# Power.net
KiCad netlist of a schematic drawn in Altium Designer
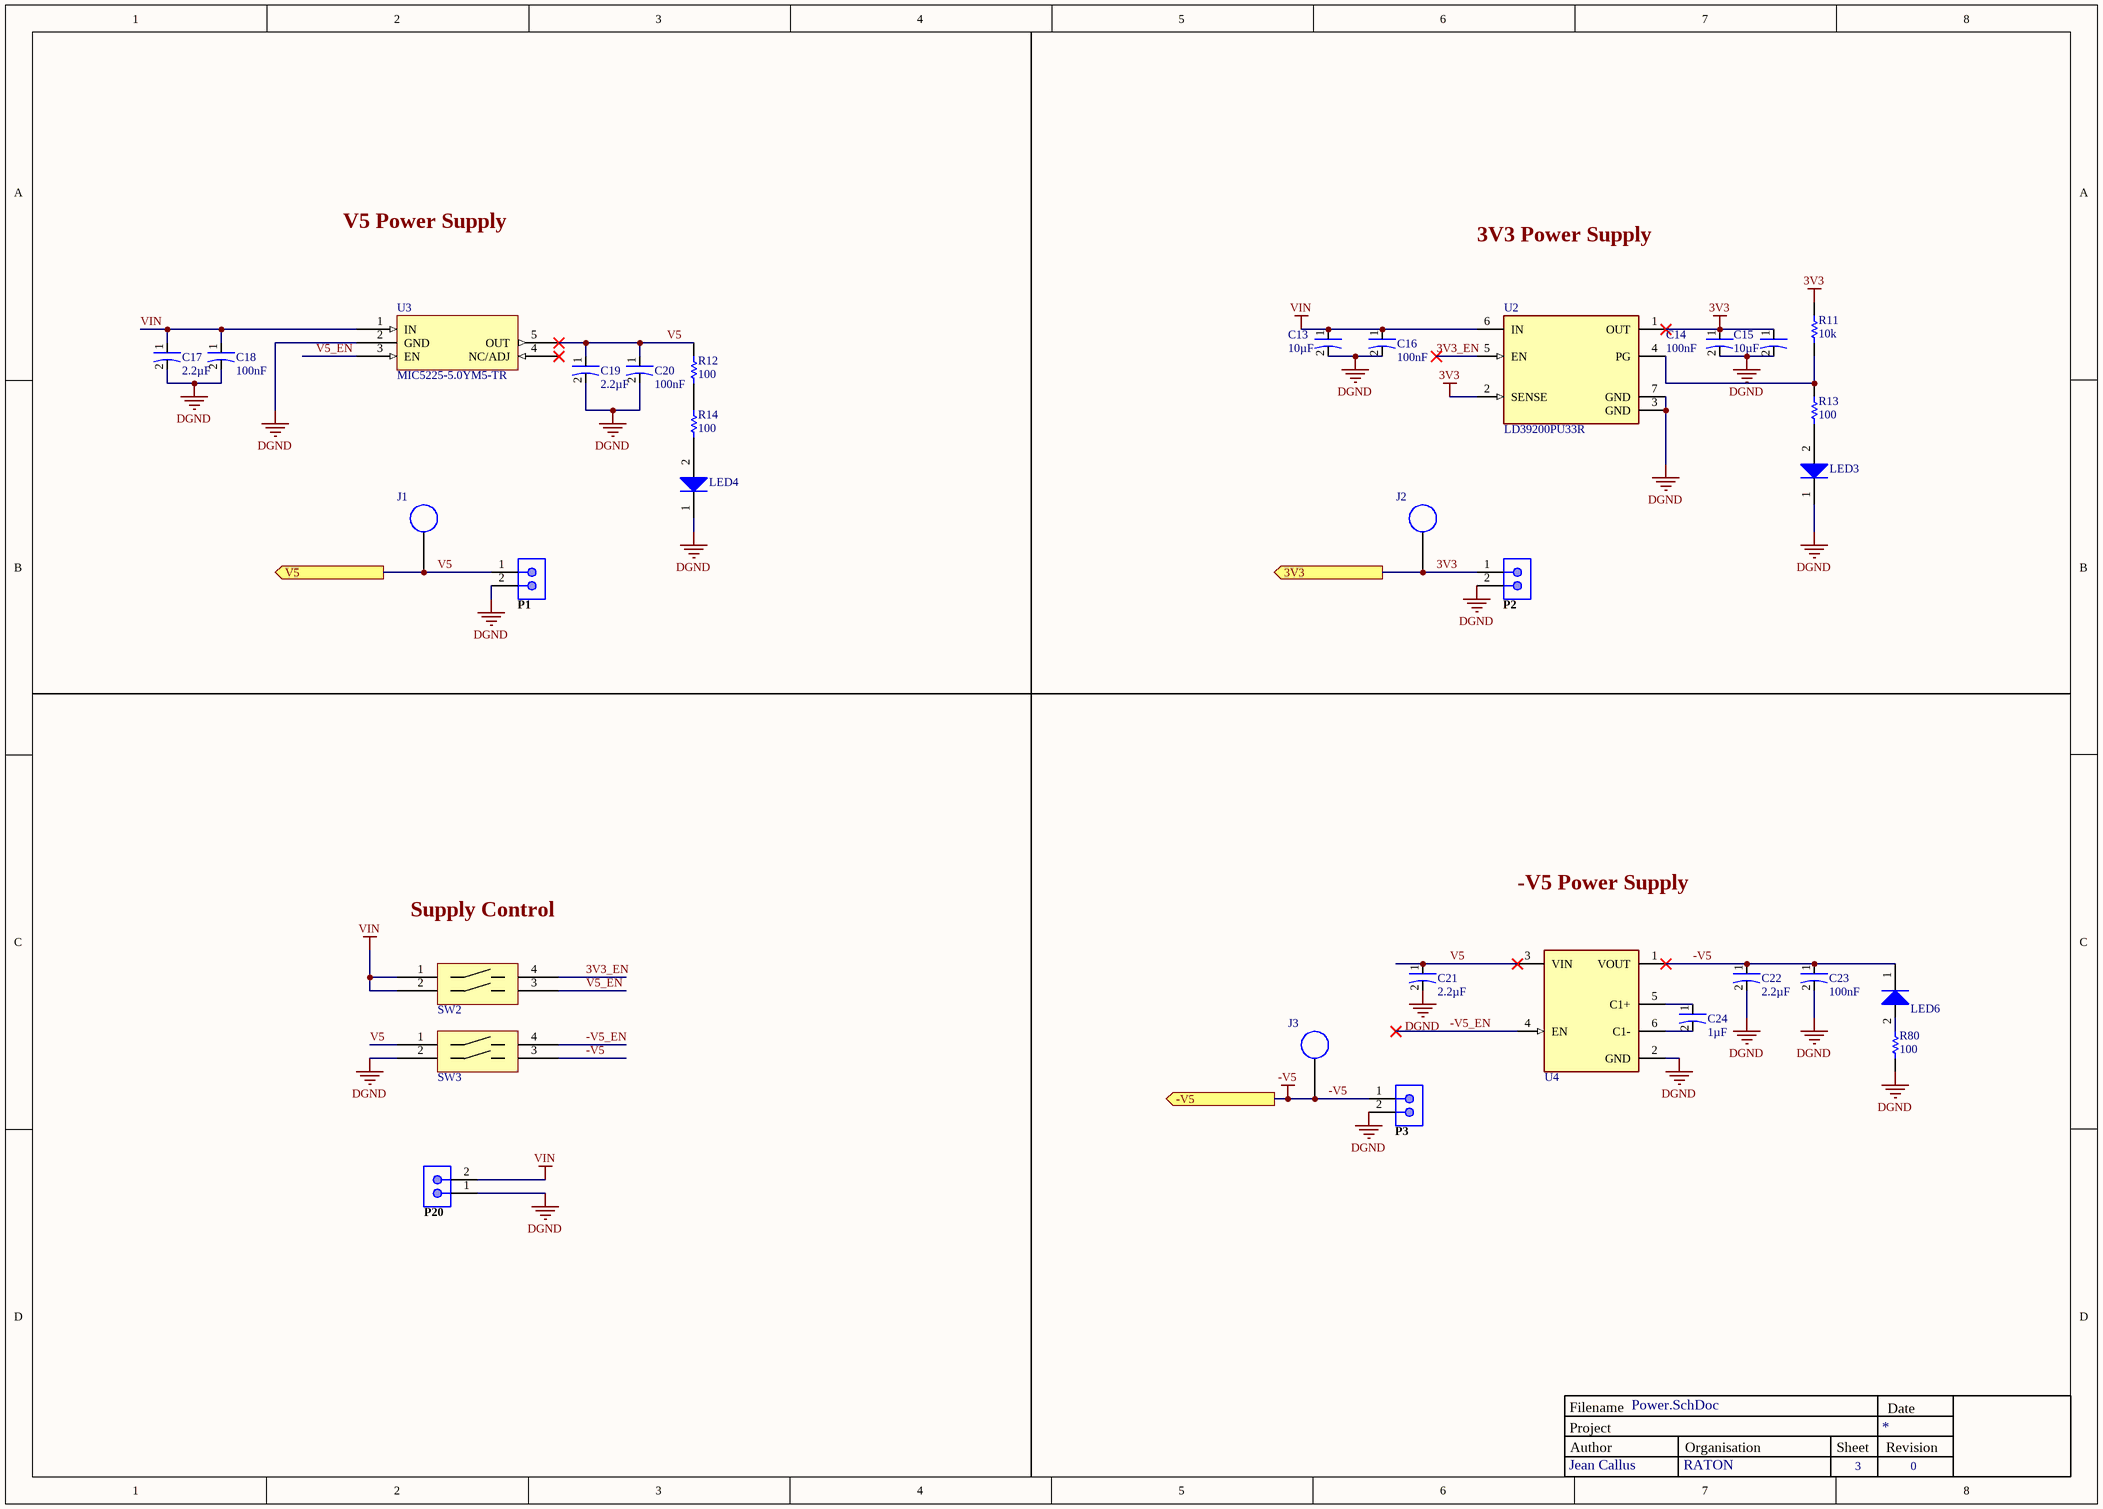
[diagram p0: Power.SchDoc]

(export (version "E")
  (design (tool "Eeschema 10.0.6"))
  (components
    (comp (ref "C13")
      (value "10µF")
      (footprint "0402-M")
      (description "CAP-10uF-CER-0402-6.3V-X5R-20%")
      (fields
        (field (name "MANUFACTURER") "Generic")
        (field (name "Comment") "CAP 10uF CER 0402 6.3V X5R 20%")
      )
      (libsource (lib "") (part "Symbol_1"))
    )
    (comp (ref "C14")
      (value "100nF")
      (footprint "0805-M")
      (description "CAP-0.1uF-CER-0805-50V-X7R-10%")
      (fields
        (field (name "MANUFACTURER") "Generic")
        (field (name "Comment") "CAP 0.1uF CER 0805 50V X7R 10%")
      )
      (libsource (lib "") (part "Symbol_1"))
    )
    (comp (ref "C15")
      (value "10µF")
      (footprint "0402-M")
      (description "CAP-10uF-CER-0402-6.3V-X5R-20%")
      (fields
        (field (name "MANUFACTURER") "Generic")
        (field (name "Comment") "CAP 10uF CER 0402 6.3V X5R 20%")
      )
      (libsource (lib "") (part "Symbol_1"))
    )
    (comp (ref "C16")
      (value "100nF")
      (footprint "0805-M")
      (description "CAP-0.1uF-CER-0805-50V-X7R-10%")
      (fields
        (field (name "MANUFACTURER") "Generic")
        (field (name "Comment") "CAP 0.1uF CER 0805 50V X7R 10%")
      )
      (libsource (lib "") (part "Symbol_1"))
    )
    (comp (ref "C17")
      (value "2.2µF")
      (footprint "0402-M")
      (description "CAP-2.2uF-CER-0402-25V-X5R-10%")
      (fields
        (field (name "MANUFACTURER") "Generic")
        (field (name "Comment") "CAP 2.2uF CER 0402 25V X5R 10%")
      )
      (libsource (lib "") (part "Symbol_1"))
    )
    (comp (ref "C18")
      (value "100nF")
      (footprint "0805-M")
      (description "CAP-0.1uF-CER-0805-50V-X7R-10%")
      (fields
        (field (name "MANUFACTURER") "Generic")
        (field (name "Comment") "CAP 0.1uF CER 0805 50V X7R 10%")
      )
      (libsource (lib "") (part "Symbol_1"))
    )
    (comp (ref "C19")
      (value "2.2µF")
      (footprint "0402-M")
      (description "CAP-2.2uF-CER-0402-25V-X5R-10%")
      (fields
        (field (name "MANUFACTURER") "Generic")
        (field (name "Comment") "CAP 2.2uF CER 0402 25V X5R 10%")
      )
      (libsource (lib "") (part "Symbol_1"))
    )
    (comp (ref "C20")
      (value "100nF")
      (footprint "0805-M")
      (description "CAP-0.1uF-CER-0805-50V-X7R-10%")
      (fields
        (field (name "MANUFACTURER") "Generic")
        (field (name "Comment") "CAP 0.1uF CER 0805 50V X7R 10%")
      )
      (libsource (lib "") (part "Symbol_1"))
    )
    (comp (ref "C21")
      (value "2.2µF")
      (footprint "0402-M")
      (description "CAP-2.2uF-CER-0402-25V-X5R-10%")
      (fields
        (field (name "MANUFACTURER") "Generic")
        (field (name "Comment") "CAP 2.2uF CER 0402 25V X5R 10%")
      )
      (libsource (lib "") (part "Symbol_1"))
    )
    (comp (ref "C22")
      (value "2.2µF")
      (footprint "0402-M")
      (description "CAP-2.2uF-CER-0402-25V-X5R-10%")
      (fields
        (field (name "MANUFACTURER") "Generic")
        (field (name "Comment") "CAP 2.2uF CER 0402 25V X5R 10%")
      )
      (libsource (lib "") (part "Symbol_1"))
    )
    (comp (ref "C23")
      (value "100nF")
      (footprint "0805-M")
      (description "CAP-0.1uF-CER-0805-50V-X7R-10%")
      (fields
        (field (name "MANUFACTURER") "Generic")
        (field (name "Comment") "CAP 0.1uF CER 0805 50V X7R 10%")
      )
      (libsource (lib "") (part "Symbol_1"))
    )
    (comp (ref "C24")
      (value "1µF")
      (footprint "0402-M")
      (description "CAP-1uF-CER-0402-25V-X5R-20%")
      (fields (field (name "MANUFACTURER") "Generic") (field (name "Comment") "CAP 1uF CER 0402 25V X5R 20%"))
      (libsource (lib "") (part "Symbol_1"))
    )
    (comp (ref "J1")
      (value "151-203-RC")
      (footprint "151-203-RC-Footprint-1")
      (description "PCB-Probe-Ring")
      (libsource (lib "University of Malta - MEMENTO") (part "PCB Probe Ring"))
    )
    (comp (ref "J2")
      (value "151-203-RC")
      (footprint "151-203-RC-Footprint-1")
      (description "PCB-Probe-Ring")
      (libsource (lib "University of Malta - MEMENTO") (part "PCB Probe Ring"))
    )
    (comp (ref "J3")
      (value "151-203-RC")
      (footprint "151-203-RC-Footprint-1")
      (description "PCB-Probe-Ring")
      (libsource (lib "University of Malta - MEMENTO") (part "PCB Probe Ring"))
    )
    (comp (ref "LED3")
      (value "LED 0603 Green 20mA 1.8V")
      (footprint "0603 Generic")
      (description "LED-0603-Green-20mA-1.8V-STOCK")
      (fields (field (name "MANUFACTURER") "Generic"))
      (libsource (lib "University of Malta - MEMENTO") (part "Symbol"))
    )
    (comp (ref "LED4")
      (value "LED 0603 Green 20mA 1.8V")
      (footprint "0603 Generic")
      (description "LED-0603-Green-20mA-1.8V-STOCK")
      (fields (field (name "MANUFACTURER") "Generic"))
      (libsource (lib "University of Malta - MEMENTO") (part "Symbol"))
    )
    (comp (ref "LED6")
      (value "LED 0603 Green 20mA 1.8V")
      (footprint "0603 Generic")
      (description "LED-0603-Green-20mA-1.8V-STOCK")
      (fields (field (name "MANUFACTURER") "Generic"))
      (libsource (lib "University of Malta - MEMENTO") (part "Symbol"))
    )
    (comp (ref "P1")
      (value "GENERIC 2PIN HEADER MALE")
      (footprint "GENERIC 2PIN HEADER 0")
      (description "CONN MAL TH 2 0Deg HEADER")
      (fields (field (name "MANUFACTURER") "Generic"))
      (libsource (lib "University of Malta - MEMENTO") (part "GENERIC 2PIN HEADER MALE"))
    )
    (comp (ref "P2")
      (value "GENERIC 2PIN HEADER MALE")
      (footprint "GENERIC 2PIN HEADER 0")
      (description "CONN MAL TH 2 0Deg HEADER")
      (fields (field (name "MANUFACTURER") "Generic"))
      (libsource (lib "University of Malta - MEMENTO") (part "GENERIC 2PIN HEADER MALE"))
    )
    (comp (ref "P3")
      (value "GENERIC 2PIN HEADER MALE")
      (footprint "GENERIC 2PIN HEADER 0")
      (description "CONN MAL TH 2 0Deg HEADER")
      (fields (field (name "MANUFACTURER") "Generic"))
      (libsource (lib "University of Malta - MEMENTO") (part "GENERIC 2PIN HEADER MALE"))
    )
    (comp (ref "P20")
      (value "GENERIC 2PIN HEADER MALE")
      (footprint "GENERIC 2PIN HEADER 0")
      (description "CONN MAL TH 2 0Deg HEADER")
      (fields (field (name "MANUFACTURER") "Generic"))
      (libsource (lib "") (part "GENERIC 2PIN HEADER MALE_1"))
    )
    (comp (ref "R11")
      (value "10k")
      (footprint "0402-M")
      (description "RES-10k-0402-63mW-5%")
      (fields (field (name "MANUFACTURER") "Generic") (field (name "Comment") "RES 10k 0402 63mW 5%"))
      (libsource (lib "") (part "Symbol_2"))
    )
    (comp (ref "R12")
      (value "100")
      (footprint "0805-L")
      (description "RES-100-0805-125mW-1%")
      (fields (field (name "MANUFACTURER") "Generic") (field (name "Comment") "RES 100 0805 125mW 1%"))
      (libsource (lib "") (part "Symbol_2"))
    )
    (comp (ref "R13")
      (value "100")
      (footprint "0805-L")
      (description "RES-100-0805-125mW-1%")
      (fields (field (name "MANUFACTURER") "Generic") (field (name "Comment") "RES 100 0805 125mW 1%"))
      (libsource (lib "") (part "Symbol_2"))
    )
    (comp (ref "R14")
      (value "100")
      (footprint "0805-L")
      (description "RES-100-0805-125mW-1%")
      (fields (field (name "MANUFACTURER") "Generic") (field (name "Comment") "RES 100 0805 125mW 1%"))
      (libsource (lib "") (part "Symbol_2"))
    )
    (comp (ref "R80")
      (value "100")
      (footprint "0805-L")
      (description "RES-100-0805-125mW-1%")
      (fields (field (name "MANUFACTURER") "Generic") (field (name "Comment") "RES 100 0805 125mW 1%"))
      (libsource (lib "") (part "Symbol_2"))
    )
    (comp (ref "SW2")
      (value "210-2MS")
      (footprint "210-2MS-Footprint-1")
      (description "SWITCH DIP SPST 2 100mA 50V")
      (libsource (lib "University of Malta - MEMENTO") (part "210-2MS"))
    )
    (comp (ref "SW3")
      (value "210-2MS")
      (footprint "210-2MS-Footprint-1")
      (description "SWITCH DIP SPST 2 100mA 50V")
      (libsource (lib "University of Malta - MEMENTO") (part "210-2MS"))
    )
    (comp (ref "U2")
      (value "LD39200PU33R")
      (footprint "FP-DFN6-7946637-MFG")
      (description "STMICROELECTRONICS - LD39200PU33R - LDO, FIXED, 3.3V, 2A, -40 TO 125DEG C")
      (fields (field (name "MANUFACTURER") "STMicroelectronics"))
      (libsource (lib "University of Malta - MEMENTO") (part "f0cfe00d12cb984572f50007c934a2d"))
    )
    (comp (ref "U3")
      (value "MIC5225-5.0YM5-TR")
      (footprint "SOT95P280X145-5N")
      (fields (field (name "MANUFACTURER") "Microchip"))
      (libsource (lib "University of Malta - MEMENTO") (part "MIC5225-5.0YM5-TR"))
    )
    (comp (ref "U4")
      (value "LM2776DBVR")
      (footprint "FP-DBV0006A-IPC_B")
      (description "Charge Pump Negative Voltage")
      (fields (field (name "MANUFACTURER") "Texas Instruments"))
      (libsource (lib "University of Malta - MEMENTO") (part "aa1f6f8daf1b38e6829d08268534e6c"))
    )
  )
  (nets
    (net (code "1") (name "-V5") (class "Default")
      (node (ref "C22") (pin "1") (pinfunction "Anode_1") (pintype "passive"))
      (node (ref "C23") (pin "1") (pinfunction "Anode_1") (pintype "passive"))
      (node (ref "J3") (pin "1") (pinfunction "1_1") (pintype "passive"))
      (node (ref "LED6") (pin "1") (pinfunction "1_1") (pintype "passive"))
      (node (ref "P3") (pin "1") (pinfunction "1_1") (pintype "passive"))
      (node (ref "SW3") (pin "3") (pinfunction "4_3") (pintype "passive"))
      (node (ref "U4") (pin "1") (pinfunction "VOUT_1") (pintype "power_in"))
    )
    (net (code "2") (name "/-V5_EN") (class "Default")
      (node (ref "SW3") (pin "4") (pinfunction "4_4") (pintype "passive"))
      (node (ref "U4") (pin "4") (pinfunction "EN_4") (pintype "input"))
    )
    (net (code "3") (name "/3V3_EN") (class "Default")
      (node (ref "SW2") (pin "4") (pinfunction "4_4") (pintype "passive"))
      (node (ref "U2") (pin "5") (pinfunction "EN_5") (pintype "input"))
    )
    (net (code "4") (name "/V5") (class "Default")
      (node (ref "C19") (pin "1") (pinfunction "Anode_1") (pintype "passive"))
      (node (ref "C20") (pin "1") (pinfunction "Anode_1") (pintype "passive"))
      (node (ref "C21") (pin "1") (pinfunction "Anode_1") (pintype "passive"))
      (node (ref "J1") (pin "1") (pinfunction "1_1") (pintype "passive"))
      (node (ref "P1") (pin "1") (pinfunction "1_1") (pintype "passive"))
      (node (ref "R12") (pin "2") (pinfunction "2_2") (pintype "passive"))
      (node (ref "SW3") (pin "1") (pinfunction "1_1") (pintype "passive"))
      (node (ref "U3") (pin "5") (pinfunction "OUT_5") (pintype "output"))
      (node (ref "U4") (pin "3") (pinfunction "VIN_3") (pintype "power_in"))
    )
    (net (code "5") (name "/V5_EN") (class "Default")
      (node (ref "SW2") (pin "3") (pinfunction "4_3") (pintype "passive"))
      (node (ref "U3") (pin "3") (pinfunction "EN_3") (pintype "input"))
    )
    (net (code "6") (name "3V3") (class "Default")
      (node (ref "C14") (pin "1") (pinfunction "Anode_1") (pintype "passive"))
      (node (ref "C15") (pin "1") (pinfunction "Anode_1") (pintype "passive"))
      (node (ref "J2") (pin "1") (pinfunction "1_1") (pintype "passive"))
      (node (ref "P2") (pin "1") (pinfunction "1_1") (pintype "passive"))
      (node (ref "R11") (pin "2") (pinfunction "2_2") (pintype "passive"))
      (node (ref "U2") (pin "1") (pinfunction "OUT_1") (pintype "power_in"))
      (node (ref "U2") (pin "2") (pinfunction "SENSE_2") (pintype "input"))
    )
    (net (code "7") (name "DGND") (class "Default")
      (node (ref "C13") (pin "2") (pinfunction "Cathode_2") (pintype "passive"))
      (node (ref "C14") (pin "2") (pinfunction "Cathode_2") (pintype "passive"))
      (node (ref "C15") (pin "2") (pinfunction "Cathode_2") (pintype "passive"))
      (node (ref "C16") (pin "2") (pinfunction "Cathode_2") (pintype "passive"))
      (node (ref "C17") (pin "2") (pinfunction "Cathode_2") (pintype "passive"))
      (node (ref "C18") (pin "2") (pinfunction "Cathode_2") (pintype "passive"))
      (node (ref "C19") (pin "2") (pinfunction "Cathode_2") (pintype "passive"))
      (node (ref "C20") (pin "2") (pinfunction "Cathode_2") (pintype "passive"))
      (node (ref "C21") (pin "2") (pinfunction "Cathode_2") (pintype "passive"))
      (node (ref "C22") (pin "2") (pinfunction "Cathode_2") (pintype "passive"))
      (node (ref "C23") (pin "2") (pinfunction "Cathode_2") (pintype "passive"))
      (node (ref "LED3") (pin "1") (pinfunction "1_1") (pintype "passive"))
      (node (ref "LED4") (pin "1") (pinfunction "1_1") (pintype "passive"))
      (node (ref "P1") (pin "2") (pinfunction "2_2") (pintype "passive"))
      (node (ref "P2") (pin "2") (pinfunction "2_2") (pintype "passive"))
      (node (ref "P20") (pin "1") (pinfunction "1_1") (pintype "passive"))
      (node (ref "P3") (pin "2") (pinfunction "2_2") (pintype "passive"))
      (node (ref "R80") (pin "1") (pinfunction "1_1") (pintype "passive"))
      (node (ref "SW3") (pin "2") (pinfunction "2_2") (pintype "passive"))
      (node (ref "U2") (pin "3") (pinfunction "GND_3") (pintype "power_in"))
      (node (ref "U2") (pin "7") (pinfunction "GND_7") (pintype "power_in"))
      (node (ref "U3") (pin "2") (pinfunction "GND_2") (pintype "power_in"))
      (node (ref "U4") (pin "2") (pinfunction "GND_2") (pintype "power_in"))
    )
    (net (code "8") (name "Net-(C24-Anode)") (class "Default")
      (node (ref "C24") (pin "1") (pinfunction "Anode_1") (pintype "passive"))
      (node (ref "U4") (pin "5") (pinfunction "C1+_5") (pintype "power_in"))
    )
    (net (code "9") (name "Net-(C24-Cathode)") (class "Default")
      (node (ref "C24") (pin "2") (pinfunction "Cathode_2") (pintype "passive"))
      (node (ref "U4") (pin "6") (pinfunction "C1-_6") (pintype "power_in"))
    )
    (net (code "10") (name "Net-(LED3-Pad2)") (class "Default")
      (node (ref "LED3") (pin "2") (pinfunction "2_2") (pintype "passive"))
      (node (ref "R13") (pin "1") (pinfunction "1_1") (pintype "passive"))
    )
    (net (code "11") (name "Net-(LED4-Pad2)") (class "Default")
      (node (ref "LED4") (pin "2") (pinfunction "2_2") (pintype "passive"))
      (node (ref "R14") (pin "1") (pinfunction "1_1") (pintype "passive"))
    )
    (net (code "12") (name "Net-(LED6-Pad2)") (class "Default")
      (node (ref "LED6") (pin "2") (pinfunction "2_2") (pintype "passive"))
      (node (ref "R80") (pin "2") (pinfunction "2_2") (pintype "passive"))
    )
    (net (code "13") (name "Net-(R12-Pad1)") (class "Default")
      (node (ref "R12") (pin "1") (pinfunction "1_1") (pintype "passive"))
      (node (ref "R14") (pin "2") (pinfunction "2_2") (pintype "passive"))
    )
    (net (code "14") (name "Net-(U2-PG)") (class "Default")
      (node (ref "R11") (pin "1") (pinfunction "1_1") (pintype "passive"))
      (node (ref "R13") (pin "2") (pinfunction "2_2") (pintype "passive"))
      (node (ref "U2") (pin "4") (pinfunction "PG_4") (pintype "open_collector"))
    )
    (net (code "15") (name "VIN") (class "Default")
      (node (ref "C13") (pin "1") (pinfunction "Anode_1") (pintype "passive"))
      (node (ref "C16") (pin "1") (pinfunction "Anode_1") (pintype "passive"))
      (node (ref "C17") (pin "1") (pinfunction "Anode_1") (pintype "passive"))
      (node (ref "C18") (pin "1") (pinfunction "Anode_1") (pintype "passive"))
      (node (ref "P20") (pin "2") (pinfunction "2_2") (pintype "passive"))
      (node (ref "SW2") (pin "1") (pinfunction "1_1") (pintype "passive"))
      (node (ref "SW2") (pin "2") (pinfunction "2_2") (pintype "passive"))
      (node (ref "U2") (pin "6") (pinfunction "IN_6") (pintype "power_in"))
      (node (ref "U3") (pin "1") (pinfunction "IN_1") (pintype "input"))
    )
    (net (code "16") (name "unconnected-(U3-NC{slash}ADJ-Pad4)") (class "Default")
      (node (ref "U3") (pin "4") (pinfunction "NC/ADJ_4") (pintype "input+no_connect"))
    )
  )
)
